# v0_2_1.net
KiCad netlist of a schematic drawn in EAGLE
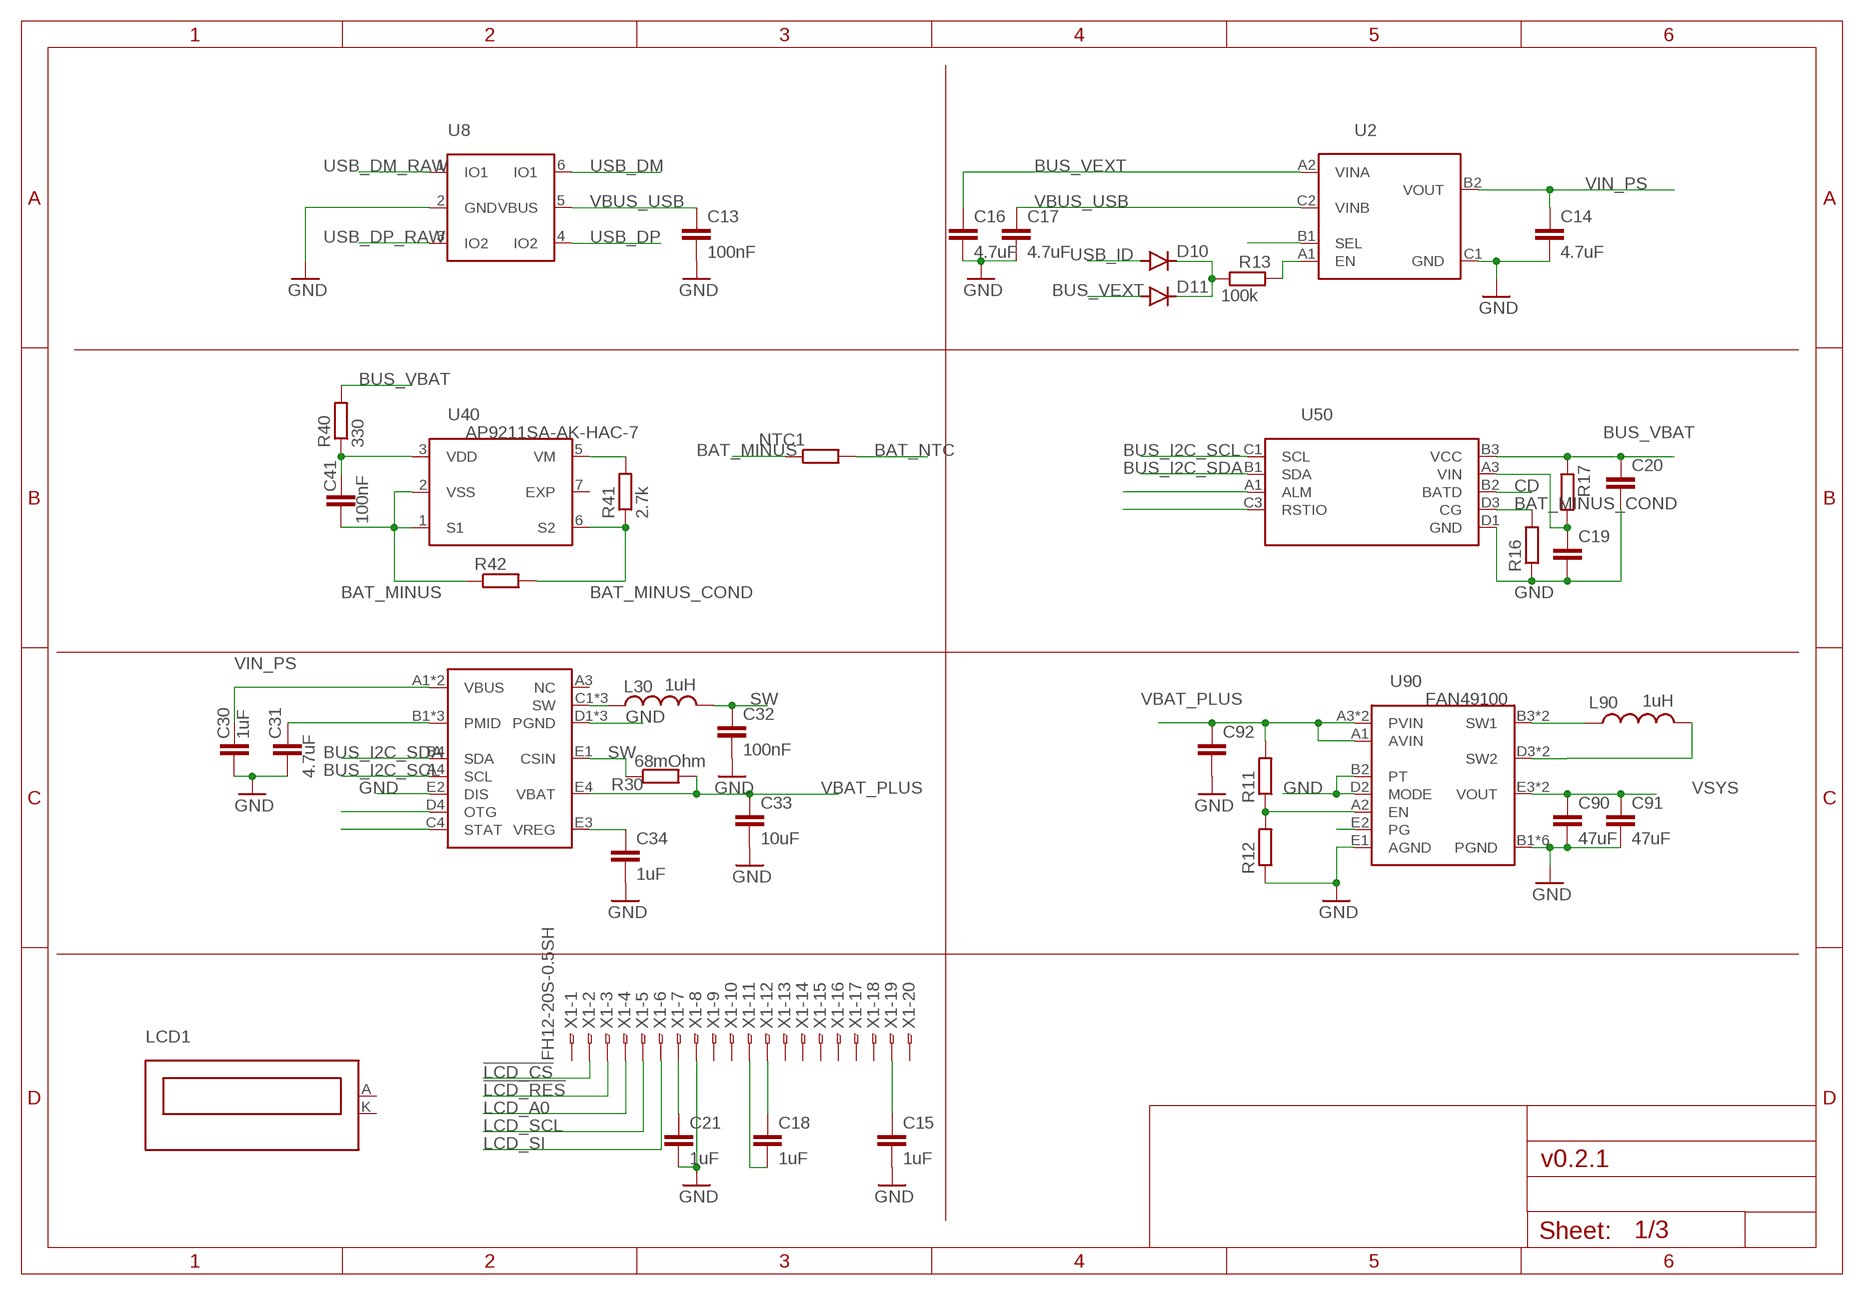
[diagram p0: schematic, sheet 1]
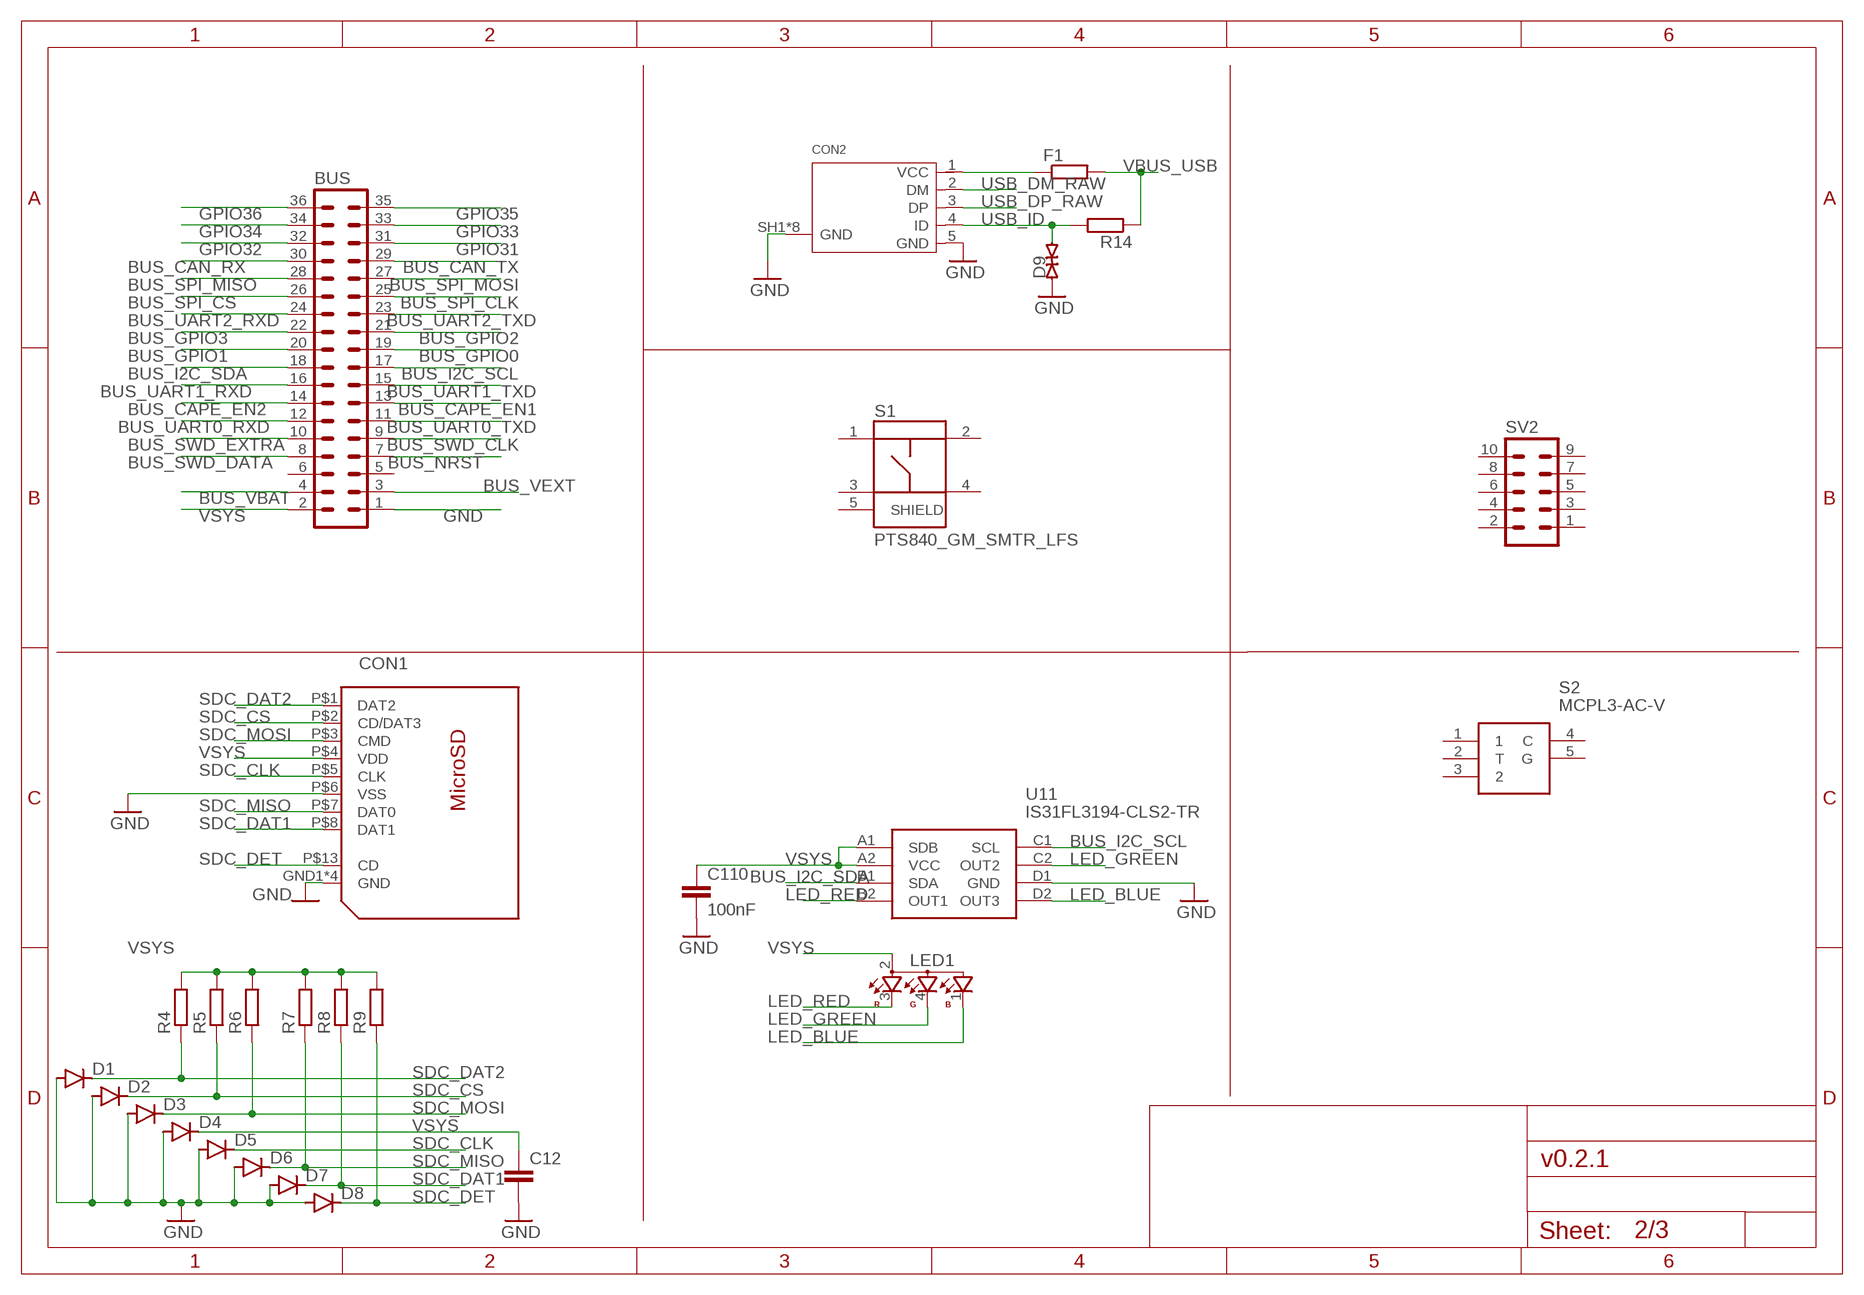
[diagram p1: schematic, sheet 2]
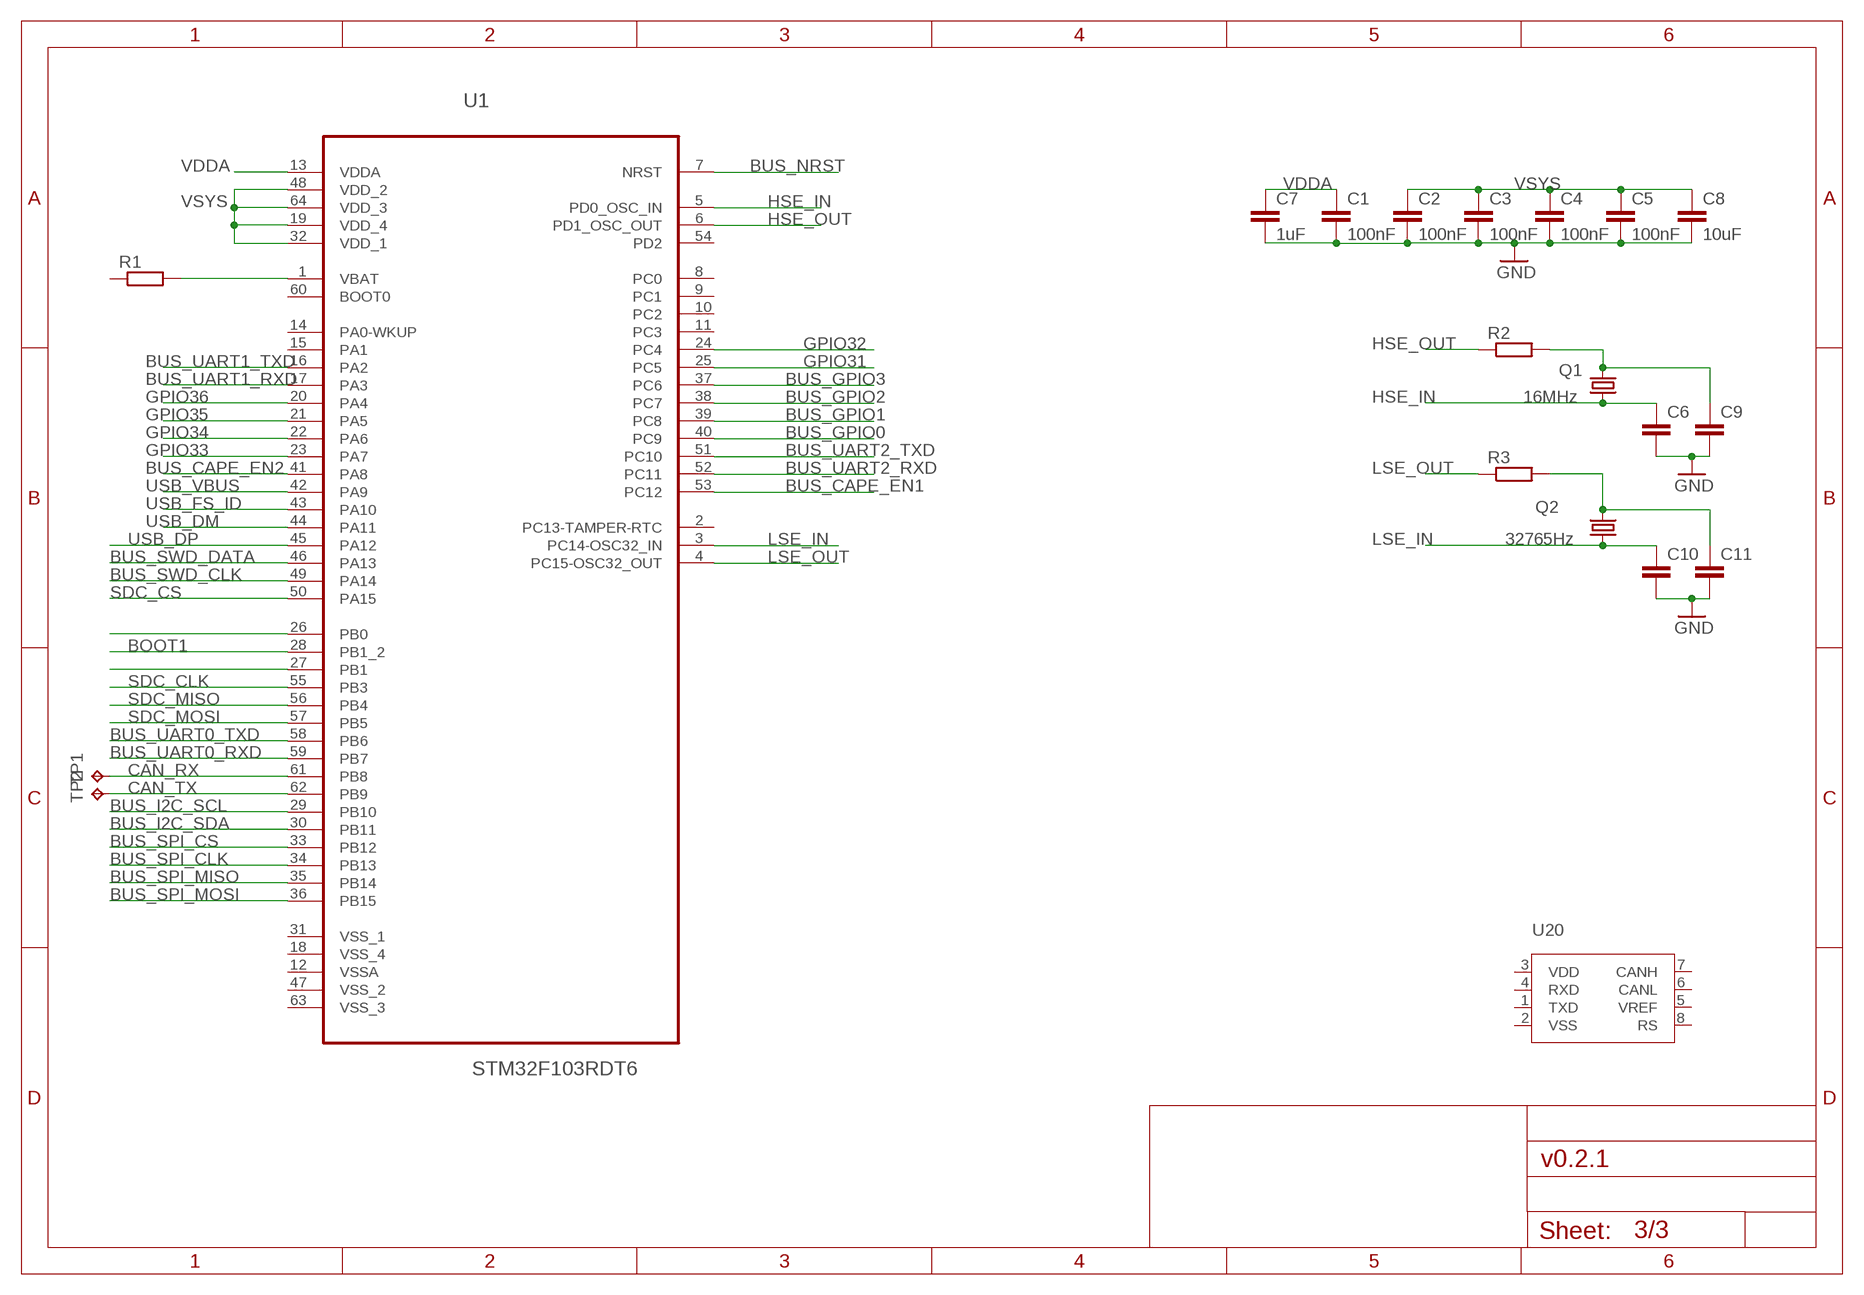
[diagram p2: schematic, sheet 3]

(export (version "E")
  (design (tool "Eeschema 10.0.6"))
  (components
    (comp (ref "C13")
      (value "100nF")
      (footprint "eagle-import:C0402")
      (libsource (lib "eagle-import") (part "C-EUC0402"))
    )
    (comp (ref "C14")
      (value "4.7uF")
      (footprint "eagle-import:C0603")
      (libsource (lib "eagle-import") (part "C-EUC0603"))
    )
    (comp (ref "C15")
      (value "1uF")
      (footprint "eagle-import:C0805")
      (libsource (lib "eagle-import") (part "C-EUC0805"))
    )
    (comp (ref "C16")
      (value "4.7uF")
      (footprint "eagle-import:C0603")
      (libsource (lib "eagle-import") (part "C-EUC0603"))
    )
    (comp (ref "C17")
      (value "4.7uF")
      (footprint "eagle-import:C0603")
      (libsource (lib "eagle-import") (part "C-EUC0603"))
    )
    (comp (ref "C18")
      (value "1uF")
      (footprint "eagle-import:C0805")
      (libsource (lib "eagle-import") (part "C-EUC0805"))
    )
    (comp (ref "C19")
      (value "C-EUC0402")
      (footprint "eagle-import:C0402")
      (libsource (lib "eagle-import") (part "C-EUC0402"))
    )
    (comp (ref "C20")
      (value "C-EUC0402")
      (footprint "eagle-import:C0402")
      (libsource (lib "eagle-import") (part "C-EUC0402"))
    )
    (comp (ref "C21")
      (value "1uF")
      (footprint "eagle-import:C0603")
      (libsource (lib "eagle-import") (part "C-EUC0603"))
    )
    (comp (ref "C30")
      (value "1uF")
      (footprint "eagle-import:C0402")
      (libsource (lib "eagle-import") (part "C-EUC0402"))
    )
    (comp (ref "C31")
      (value "4.7uF")
      (footprint "eagle-import:C0603")
      (libsource (lib "eagle-import") (part "C-EUC0603"))
    )
    (comp (ref "C32")
      (value "100nF")
      (footprint "eagle-import:C0402")
      (libsource (lib "eagle-import") (part "C-EUC0402"))
    )
    (comp (ref "C33")
      (value "10uF")
      (footprint "eagle-import:C0603")
      (libsource (lib "eagle-import") (part "C-EUC0603"))
    )
    (comp (ref "C34")
      (value "1uF")
      (footprint "eagle-import:C0402")
      (libsource (lib "eagle-import") (part "C-EUC0402"))
    )
    (comp (ref "C41")
      (value "100nF")
      (footprint "eagle-import:C0402")
      (libsource (lib "eagle-import") (part "C-EUC0402"))
    )
    (comp (ref "C90")
      (value "47uF")
      (footprint "eagle-import:C0805")
      (libsource (lib "eagle-import") (part "C-EUC0805"))
    )
    (comp (ref "C91")
      (value "47uF")
      (footprint "eagle-import:C0805")
      (libsource (lib "eagle-import") (part "C-EUC0805"))
    )
    (comp (ref "C92")
      (value "C-EUC0805")
      (footprint "eagle-import:C0805")
      (libsource (lib "eagle-import") (part "C-EUC0805"))
    )
    (comp (ref "D10")
      (value "DIODE-SOD523")
      (footprint "eagle-import:SOD523")
      (libsource (lib "eagle-import") (part "DIODE-SOD523"))
    )
    (comp (ref "D11")
      (value "DIODE-SOD523")
      (footprint "eagle-import:SOD523")
      (libsource (lib "eagle-import") (part "DIODE-SOD523"))
    )
    (comp (ref "L30")
      (value "1uH")
      (footprint "eagle-import:L3230M")
      (libsource (lib "eagle-import") (part "DJNR3015"))
    )
    (comp (ref "L90")
      (value "1uH")
      (footprint "eagle-import:L3230M")
      (libsource (lib "eagle-import") (part "DJNR3015"))
    )
    (comp (ref "LCD1")
      (value "DEM-128064P-FGH-PW")
      (footprint "eagle-import:DEM128064PFGH-PW")
      (libsource (lib "eagle-import") (part "DEM-128064P-FGH-PW"))
    )
    (comp (ref "NTC1")
      (value "R-EU_R0603")
      (footprint "eagle-import:R0603")
      (libsource (lib "eagle-import") (part "R-EU_R0603"))
    )
    (comp (ref "R11")
      (value "R-EU_R0402")
      (footprint "eagle-import:R0402")
      (libsource (lib "eagle-import") (part "R-EU_R0402"))
    )
    (comp (ref "R12")
      (value "R-EU_R0402")
      (footprint "eagle-import:R0402")
      (libsource (lib "eagle-import") (part "R-EU_R0402"))
    )
    (comp (ref "R13")
      (value "100k")
      (footprint "eagle-import:R0402")
      (libsource (lib "eagle-import") (part "R-EU_R0402"))
    )
    (comp (ref "R16")
      (value "R-EU_R0805")
      (footprint "eagle-import:R0805")
      (libsource (lib "eagle-import") (part "R-EU_R0805"))
    )
    (comp (ref "R17")
      (value "R-EU_R0402")
      (footprint "eagle-import:R0402")
      (libsource (lib "eagle-import") (part "R-EU_R0402"))
    )
    (comp (ref "R30")
      (value "68mOhm")
      (footprint "eagle-import:R0805")
      (libsource (lib "eagle-import") (part "R-EU_R0805"))
    )
    (comp (ref "R40")
      (value "330")
      (footprint "eagle-import:R0402")
      (libsource (lib "eagle-import") (part "R-EU_R0402"))
    )
    (comp (ref "R41")
      (value "2.7k")
      (footprint "eagle-import:R0402")
      (libsource (lib "eagle-import") (part "R-EU_R0402"))
    )
    (comp (ref "R42")
      (value "R-EU_R0603")
      (footprint "eagle-import:R0603")
      (libsource (lib "eagle-import") (part "R-EU_R0603"))
    )
    (comp (ref "U2")
      (value "FPF1320")
      (footprint "eagle-import:BGA6C50P2X3_146X96X60")
      (libsource (lib "eagle-import") (part "FPF1320"))
    )
    (comp (ref "U8")
      (value "USBLC6-2P6")
      (footprint "eagle-import:SOTFL50P160X60-6")
      (libsource (lib "eagle-import") (part "USBLC6-2P6"))
    )
    (comp (ref "U30")
      (value "FAN54015")
      (footprint "eagle-import:BGA20C40P4X5_196X187X55")
      (libsource (lib "eagle-import") (part "FAN54015"))
    )
    (comp (ref "U40")
      (value "AP9211SA-AK-HAC-7")
      (footprint "eagle-import:DFN200X300X60-7N")
      (fields (field (name "MF") "Diodes Inc."))
      (libsource (lib "eagle-import") (part "AP9211SA-AK-HAC-7"))
    )
    (comp (ref "U50")
      (value "STC3115")
      (footprint "eagle-import:BGA12C40P4X3_137X201X65")
      (libsource (lib "eagle-import") (part "STC3115"))
    )
    (comp (ref "U90")
      (value "FAN49100")
      (footprint "eagle-import:BGA20C40P4X5_201X161X60")
      (libsource (lib "eagle-import") (part "FAN49100"))
    )
    (comp (ref "X1")
      (value "FH12-20S-0.5SH")
      (footprint "eagle-import:FH12-20S-0.5SH")
      (fields (field (name "MPN") "FH12-20S-0.5SH(55)"))
      (libsource (lib "eagle-import") (part "FH12-20S-0.5SH"))
    )
    (comp (ref "BUS")
      (value "MA18-2")
      (footprint "eagle-import:MA18-2")
      (libsource (lib "eagle-import") (part "MA18-2"))
    )
    (comp (ref "C12")
      (value "C-EUC0402")
      (footprint "eagle-import:C0402")
      (libsource (lib "eagle-import") (part "C-EUC0402"))
    )
    (comp (ref "C110")
      (value "100nF")
      (footprint "eagle-import:C0402")
      (libsource (lib "eagle-import") (part "C-EUC0402"))
    )
    (comp (ref "CON1")
      (value "112J-TXAR")
      (footprint "eagle-import:112J")
      (libsource (lib "eagle-import") (part "112J-TXAR"))
    )
    (comp (ref "CON2")
      (value "10118194-0001LF")
      (footprint "eagle-import:10118194")
      (libsource (lib "eagle-import") (part "10118194-0001LF"))
    )
    (comp (ref "D1")
      (value "DIODE-SOD523")
      (footprint "eagle-import:SOD523")
      (libsource (lib "eagle-import") (part "DIODE-SOD523"))
    )
    (comp (ref "D2")
      (value "DIODE-SOD523")
      (footprint "eagle-import:SOD523")
      (libsource (lib "eagle-import") (part "DIODE-SOD523"))
    )
    (comp (ref "D3")
      (value "DIODE-SOD523")
      (footprint "eagle-import:SOD523")
      (libsource (lib "eagle-import") (part "DIODE-SOD523"))
    )
    (comp (ref "D4")
      (value "DIODE-SOD523")
      (footprint "eagle-import:SOD523")
      (libsource (lib "eagle-import") (part "DIODE-SOD523"))
    )
    (comp (ref "D5")
      (value "DIODE-SOD523")
      (footprint "eagle-import:SOD523")
      (libsource (lib "eagle-import") (part "DIODE-SOD523"))
    )
    (comp (ref "D6")
      (value "DIODE-SOD523")
      (footprint "eagle-import:SOD523")
      (libsource (lib "eagle-import") (part "DIODE-SOD523"))
    )
    (comp (ref "D7")
      (value "DIODE-SOD523")
      (footprint "eagle-import:SOD523")
      (libsource (lib "eagle-import") (part "DIODE-SOD523"))
    )
    (comp (ref "D8")
      (value "DIODE-SOD523")
      (footprint "eagle-import:SOD523")
      (libsource (lib "eagle-import") (part "DIODE-SOD523"))
    )
    (comp (ref "D9")
      (value "ESD9B5.0ST5G")
      (footprint "eagle-import:SOD1006X40")
      (libsource (lib "eagle-import") (part "ESD9B5.0ST5G"))
    )
    (comp (ref "F1")
      (value "R-EU_R0603")
      (footprint "eagle-import:R0603")
      (libsource (lib "eagle-import") (part "R-EU_R0603"))
    )
    (comp (ref "LED1")
      (value "OSTB1204C1E")
      (footprint "eagle-import:321015RGB")
      (libsource (lib "eagle-import") (part "OSTB1204C1E"))
    )
    (comp (ref "R4")
      (value "R-EU_R0402")
      (footprint "eagle-import:R0402")
      (libsource (lib "eagle-import") (part "R-EU_R0402"))
    )
    (comp (ref "R5")
      (value "R-EU_R0402")
      (footprint "eagle-import:R0402")
      (libsource (lib "eagle-import") (part "R-EU_R0402"))
    )
    (comp (ref "R6")
      (value "R-EU_R0402")
      (footprint "eagle-import:R0402")
      (libsource (lib "eagle-import") (part "R-EU_R0402"))
    )
    (comp (ref "R7")
      (value "R-EU_R0402")
      (footprint "eagle-import:R0402")
      (libsource (lib "eagle-import") (part "R-EU_R0402"))
    )
    (comp (ref "R8")
      (value "R-EU_R0402")
      (footprint "eagle-import:R0402")
      (libsource (lib "eagle-import") (part "R-EU_R0402"))
    )
    (comp (ref "R9")
      (value "R-EU_R0402")
      (footprint "eagle-import:R0402")
      (libsource (lib "eagle-import") (part "R-EU_R0402"))
    )
    (comp (ref "R14")
      (value "R-EU_R0402")
      (footprint "eagle-import:R0402")
      (libsource (lib "eagle-import") (part "R-EU_R0402"))
    )
    (comp (ref "S1")
      (value "PTS840_GM_SMTR_LFS")
      (footprint "eagle-import:SW_PTS840GMSMTRLFS")
      (fields (field (name "MF") "C&K") (field (name "MP") "PTS840 GM SMTR LFS"))
      (libsource (lib "eagle-import") (part "PTS840_GM_SMTR_LFS"))
    )
    (comp (ref "S2")
      (value "MCPL3-AC-V")
      (footprint "eagle-import:MCPL3-AC-V")
      (libsource (lib "eagle-import") (part "MCPL3-AC-V"))
    )
    (comp (ref "SV2")
      (value "MA05-2")
      (footprint "eagle-import:MA05-2")
      (libsource (lib "eagle-import") (part "MA05-2"))
    )
    (comp (ref "U11")
      (value "IS31FL3194-CLS2-TR")
      (footprint "eagle-import:BGA8C40P2X4_99X159X42")
      (fields (field (name "MOUSER_PART_NUMBER") "870-IS31FL3194CLS2TR"))
      (libsource (lib "eagle-import") (part "IS31FL3194-CLS2-TR"))
    )
    (comp (ref "C1")
      (value "100nF")
      (footprint "eagle-import:C0402")
      (libsource (lib "eagle-import") (part "C-EUC0402"))
    )
    (comp (ref "C2")
      (value "100nF")
      (footprint "eagle-import:C0402")
      (libsource (lib "eagle-import") (part "C-EUC0402"))
    )
    (comp (ref "C3")
      (value "100nF")
      (footprint "eagle-import:C0402")
      (libsource (lib "eagle-import") (part "C-EUC0402"))
    )
    (comp (ref "C4")
      (value "100nF")
      (footprint "eagle-import:C0402")
      (libsource (lib "eagle-import") (part "C-EUC0402"))
    )
    (comp (ref "C5")
      (value "100nF")
      (footprint "eagle-import:C0402")
      (libsource (lib "eagle-import") (part "C-EUC0402"))
    )
    (comp (ref "C6")
      (value "C-EUC0402")
      (footprint "eagle-import:C0402")
      (libsource (lib "eagle-import") (part "C-EUC0402"))
    )
    (comp (ref "C7")
      (value "1uF")
      (footprint "eagle-import:C0402")
      (libsource (lib "eagle-import") (part "C-EUC0402"))
    )
    (comp (ref "C8")
      (value "10uF")
      (footprint "eagle-import:C0603")
      (libsource (lib "eagle-import") (part "C-EUC0603"))
    )
    (comp (ref "C9")
      (value "C-EUC0402")
      (footprint "eagle-import:C0402")
      (libsource (lib "eagle-import") (part "C-EUC0402"))
    )
    (comp (ref "C10")
      (value "C-EUC0402")
      (footprint "eagle-import:C0402")
      (libsource (lib "eagle-import") (part "C-EUC0402"))
    )
    (comp (ref "C11")
      (value "C-EUC0402")
      (footprint "eagle-import:C0402")
      (libsource (lib "eagle-import") (part "C-EUC0402"))
    )
    (comp (ref "Q1")
      (value "16MHz")
      (footprint "eagle-import:3.2X2.5_KX-7")
      (libsource (lib "eagle-import") (part "KX-7"))
    )
    (comp (ref "Q2")
      (value "32765Hz")
      (footprint "eagle-import:3.2X1.5")
      (libsource (lib "eagle-import") (part "KX-327-NHF"))
    )
    (comp (ref "R1")
      (value "R-EU_R0402")
      (footprint "eagle-import:R0402")
      (libsource (lib "eagle-import") (part "R-EU_R0402"))
    )
    (comp (ref "R2")
      (value "R-EU_R0402")
      (footprint "eagle-import:R0402")
      (libsource (lib "eagle-import") (part "R-EU_R0402"))
    )
    (comp (ref "R3")
      (value "R-EU_R0402")
      (footprint "eagle-import:R0402")
      (libsource (lib "eagle-import") (part "R-EU_R0402"))
    )
    (comp (ref "TP1")
      (value "TPB1,27")
      (footprint "eagle-import:B1,27")
      (libsource (lib "eagle-import") (part "TPB1,27"))
    )
    (comp (ref "TP2")
      (value "TPB1,27")
      (footprint "eagle-import:B1,27")
      (libsource (lib "eagle-import") (part "TPB1,27"))
    )
    (comp (ref "U1")
      (value "STM32F103RDT6")
      (footprint "eagle-import:QFP50P1200X1200X160-64N")
      (fields (field (name "MF") "STMicroelectronics"))
      (libsource (lib "eagle-import") (part "STM32F103RDT6"))
    )
    (comp (ref "U20")
      (value "MCP2551")
      (footprint "eagle-import:SOIC8")
      (libsource (lib "eagle-import") (part "MCP2551"))
    )
  )
  (nets
    (net (code "1") (name "BAT_MINUS") (class "Default")
      (node (ref "C41") (pin "2") (pinfunction "2_2") (pintype "passive"))
      (node (ref "NTC1") (pin "1") (pinfunction "1_1") (pintype "passive"))
      (node (ref "R42") (pin "1") (pinfunction "1_1") (pintype "passive"))
      (node (ref "U40") (pin "1") (pinfunction "S1_1") (pintype "output"))
      (node (ref "U40") (pin "2") (pinfunction "VSS_2") (pintype "power_in"))
    )
    (net (code "2") (name "BAT_MINUS_COND") (class "Default")
      (node (ref "R16") (pin "2") (pinfunction "2_2") (pintype "passive"))
      (node (ref "R41") (pin "1") (pinfunction "1_1") (pintype "passive"))
      (node (ref "R42") (pin "2") (pinfunction "2_2") (pintype "passive"))
      (node (ref "U40") (pin "6") (pinfunction "S2_6") (pintype "output"))
      (node (ref "U50") (pin "D3") (pinfunction "CG_D3") (pintype "bidirectional"))
    )
    (net (code "3") (name "BAT_NTC") (class "Default")
      (node (ref "NTC1") (pin "2") (pinfunction "2_2") (pintype "passive"))
    )
    (net (code "4") (name "BOOT1") (class "Default")
      (node (ref "U1") (pin "28") (pinfunction "PB1_2_28") (pintype "bidirectional"))
    )
    (net (code "5") (name "BUS_CAN_RX") (class "Default")
      (node (ref "BUS") (pin "30") (pinfunction "30_30") (pintype "passive"))
    )
    (net (code "6") (name "BUS_CAN_TX") (class "Default")
      (node (ref "BUS") (pin "29") (pinfunction "29_29") (pintype "passive"))
    )
    (net (code "7") (name "BUS_CAPE_EN1") (class "Default")
      (node (ref "BUS") (pin "13") (pinfunction "13_13") (pintype "passive"))
      (node (ref "U1") (pin "53") (pinfunction "PC12_53") (pintype "bidirectional"))
    )
    (net (code "8") (name "BUS_CAPE_EN2") (class "Default")
      (node (ref "BUS") (pin "14") (pinfunction "14_14") (pintype "passive"))
      (node (ref "U1") (pin "41") (pinfunction "PA8_41") (pintype "bidirectional"))
    )
    (net (code "9") (name "BUS_GPIO0") (class "Default")
      (node (ref "BUS") (pin "19") (pinfunction "19_19") (pintype "passive"))
      (node (ref "U1") (pin "40") (pinfunction "PC9_40") (pintype "bidirectional"))
    )
    (net (code "10") (name "BUS_GPIO1") (class "Default")
      (node (ref "BUS") (pin "20") (pinfunction "20_20") (pintype "passive"))
      (node (ref "U1") (pin "39") (pinfunction "PC8_39") (pintype "bidirectional"))
    )
    (net (code "11") (name "BUS_GPIO2") (class "Default")
      (node (ref "BUS") (pin "21") (pinfunction "21_21") (pintype "passive"))
      (node (ref "U1") (pin "38") (pinfunction "PC7_38") (pintype "bidirectional"))
    )
    (net (code "12") (name "BUS_GPIO3") (class "Default")
      (node (ref "BUS") (pin "22") (pinfunction "22_22") (pintype "passive"))
      (node (ref "U1") (pin "37") (pinfunction "PC6_37") (pintype "bidirectional"))
    )
    (net (code "13") (name "BUS_I2C_SCL") (class "Default")
      (node (ref "BUS") (pin "17") (pinfunction "17_17") (pintype "passive"))
      (node (ref "U1") (pin "29") (pinfunction "PB10_29") (pintype "bidirectional"))
      (node (ref "U11") (pin "C1") (pinfunction "SCL_C1") (pintype "bidirectional"))
      (node (ref "U30") (pin "A4") (pinfunction "SCL_A4") (pintype "bidirectional"))
      (node (ref "U50") (pin "C1") (pinfunction "SCL_C1") (pintype "bidirectional"))
    )
    (net (code "14") (name "BUS_I2C_SDA") (class "Default")
      (node (ref "BUS") (pin "18") (pinfunction "18_18") (pintype "passive"))
      (node (ref "U1") (pin "30") (pinfunction "PB11_30") (pintype "bidirectional"))
      (node (ref "U11") (pin "B1") (pinfunction "SDA_B1") (pintype "bidirectional"))
      (node (ref "U30") (pin "B4") (pinfunction "SDA_B4") (pintype "bidirectional"))
      (node (ref "U50") (pin "B1") (pinfunction "SDA_B1") (pintype "bidirectional"))
    )
    (net (code "15") (name "BUS_NRST") (class "Default")
      (node (ref "BUS") (pin "7") (pinfunction "7_7") (pintype "passive"))
      (node (ref "U1") (pin "7") (pinfunction "NRST_7") (pintype "output"))
    )
    (net (code "16") (name "BUS_SPI_CLK") (class "Default")
      (node (ref "BUS") (pin "25") (pinfunction "25_25") (pintype "passive"))
      (node (ref "U1") (pin "34") (pinfunction "PB13_34") (pintype "bidirectional"))
    )
    (net (code "17") (name "BUS_SPI_CS") (class "Default")
      (node (ref "BUS") (pin "26") (pinfunction "26_26") (pintype "passive"))
      (node (ref "U1") (pin "33") (pinfunction "PB12_33") (pintype "bidirectional"))
    )
    (net (code "18") (name "BUS_SPI_MISO") (class "Default")
      (node (ref "BUS") (pin "28") (pinfunction "28_28") (pintype "passive"))
      (node (ref "U1") (pin "35") (pinfunction "PB14_35") (pintype "bidirectional"))
    )
    (net (code "19") (name "BUS_SPI_MOSI") (class "Default")
      (node (ref "BUS") (pin "27") (pinfunction "27_27") (pintype "passive"))
      (node (ref "U1") (pin "36") (pinfunction "PB15_36") (pintype "bidirectional"))
    )
    (net (code "20") (name "BUS_SWD_CLK") (class "Default")
      (node (ref "BUS") (pin "9") (pinfunction "9_9") (pintype "passive"))
      (node (ref "U1") (pin "49") (pinfunction "PA14_49") (pintype "bidirectional"))
    )
    (net (code "21") (name "BUS_SWD_DATA") (class "Default")
      (node (ref "BUS") (pin "8") (pinfunction "8_8") (pintype "passive"))
      (node (ref "U1") (pin "46") (pinfunction "PA13_46") (pintype "bidirectional"))
    )
    (net (code "22") (name "BUS_SWD_EXTRA") (class "Default")
      (node (ref "BUS") (pin "10") (pinfunction "10_10") (pintype "passive"))
    )
    (net (code "23") (name "BUS_UART0_RXD") (class "Default")
      (node (ref "BUS") (pin "12") (pinfunction "12_12") (pintype "passive"))
      (node (ref "U1") (pin "59") (pinfunction "PB7_59") (pintype "power_in"))
    )
    (net (code "24") (name "BUS_UART0_TXD") (class "Default")
      (node (ref "BUS") (pin "11") (pinfunction "11_11") (pintype "passive"))
      (node (ref "U1") (pin "58") (pinfunction "PB6_58") (pintype "bidirectional"))
    )
    (net (code "25") (name "BUS_UART1_RXD") (class "Default")
      (node (ref "BUS") (pin "16") (pinfunction "16_16") (pintype "passive"))
      (node (ref "U1") (pin "17") (pinfunction "PA3_17") (pintype "bidirectional"))
    )
    (net (code "26") (name "BUS_UART1_TXD") (class "Default")
      (node (ref "BUS") (pin "15") (pinfunction "15_15") (pintype "passive"))
      (node (ref "U1") (pin "16") (pinfunction "PA2_16") (pintype "bidirectional"))
    )
    (net (code "27") (name "BUS_UART2_RXD") (class "Default")
      (node (ref "BUS") (pin "24") (pinfunction "24_24") (pintype "passive"))
      (node (ref "U1") (pin "52") (pinfunction "PC11_52") (pintype "bidirectional"))
    )
    (net (code "28") (name "BUS_UART2_TXD") (class "Default")
      (node (ref "BUS") (pin "23") (pinfunction "23_23") (pintype "passive"))
      (node (ref "U1") (pin "51") (pinfunction "PC10_51") (pintype "bidirectional"))
    )
    (net (code "29") (name "BUS_VBAT") (class "Default")
      (node (ref "BUS") (pin "4") (pinfunction "4_4") (pintype "passive"))
      (node (ref "C20") (pin "1") (pinfunction "1_1") (pintype "passive"))
      (node (ref "R17") (pin "1") (pinfunction "1_1") (pintype "passive"))
      (node (ref "R40") (pin "2") (pinfunction "2_2") (pintype "passive"))
      (node (ref "U50") (pin "B3") (pinfunction "VCC_B3") (pintype "bidirectional"))
    )
    (net (code "30") (name "BUS_VEXT") (class "Default")
      (node (ref "BUS") (pin "3") (pinfunction "3_3") (pintype "passive"))
      (node (ref "C16") (pin "1") (pinfunction "1_1") (pintype "passive"))
      (node (ref "D11") (pin "A") (pinfunction "A_A") (pintype "passive"))
      (node (ref "U2") (pin "A2") (pinfunction "VINA_A2") (pintype "bidirectional"))
    )
    (net (code "31") (name "CAN_RX") (class "Default")
      (node (ref "TP1") (pin "TP") (pinfunction "TP_TP") (pintype "input"))
      (node (ref "U1") (pin "61") (pinfunction "PB8_61") (pintype "bidirectional"))
    )
    (net (code "32") (name "CAN_TX") (class "Default")
      (node (ref "TP2") (pin "TP") (pinfunction "TP_TP") (pintype "input"))
      (node (ref "U1") (pin "62") (pinfunction "PB9_62") (pintype "bidirectional"))
    )
    (net (code "33") (name "CD") (class "Default")
      (node (ref "U50") (pin "B2") (pinfunction "BATD_B2") (pintype "bidirectional"))
    )
    (net (code "34") (name "EXP") (class "Default")
      (node (ref "U40") (pin "7") (pinfunction "EXP_7") (pintype "power_in"))
    )
    (net (code "35") (name "GND") (class "Default")
      (node (ref "BUS") (pin "1") (pinfunction "1_1") (pintype "passive"))
      (node (ref "C1") (pin "2") (pinfunction "2_2") (pintype "passive"))
      (node (ref "C10") (pin "2") (pinfunction "2_2") (pintype "passive"))
      (node (ref "C11") (pin "2") (pinfunction "2_2") (pintype "passive"))
      (node (ref "C110") (pin "2") (pinfunction "2_2") (pintype "passive"))
      (node (ref "C12") (pin "2") (pinfunction "2_2") (pintype "passive"))
      (node (ref "C13") (pin "2") (pinfunction "2_2") (pintype "passive"))
      (node (ref "C14") (pin "2") (pinfunction "2_2") (pintype "passive"))
      (node (ref "C15") (pin "2") (pinfunction "2_2") (pintype "passive"))
      (node (ref "C16") (pin "2") (pinfunction "2_2") (pintype "passive"))
      (node (ref "C17") (pin "2") (pinfunction "2_2") (pintype "passive"))
      (node (ref "C19") (pin "2") (pinfunction "2_2") (pintype "passive"))
      (node (ref "C2") (pin "2") (pinfunction "2_2") (pintype "passive"))
      (node (ref "C20") (pin "2") (pinfunction "2_2") (pintype "passive"))
      (node (ref "C21") (pin "2") (pinfunction "2_2") (pintype "passive"))
      (node (ref "C3") (pin "2") (pinfunction "2_2") (pintype "passive"))
      (node (ref "C30") (pin "2") (pinfunction "2_2") (pintype "passive"))
      (node (ref "C31") (pin "2") (pinfunction "2_2") (pintype "passive"))
      (node (ref "C32") (pin "2") (pinfunction "2_2") (pintype "passive"))
      (node (ref "C33") (pin "2") (pinfunction "2_2") (pintype "passive"))
      (node (ref "C34") (pin "2") (pinfunction "2_2") (pintype "passive"))
      (node (ref "C4") (pin "2") (pinfunction "2_2") (pintype "passive"))
      (node (ref "C5") (pin "2") (pinfunction "2_2") (pintype "passive"))
      (node (ref "C6") (pin "2") (pinfunction "2_2") (pintype "passive"))
      (node (ref "C7") (pin "2") (pinfunction "2_2") (pintype "passive"))
      (node (ref "C8") (pin "2") (pinfunction "2_2") (pintype "passive"))
      (node (ref "C9") (pin "2") (pinfunction "2_2") (pintype "passive"))
      (node (ref "C90") (pin "2") (pinfunction "2_2") (pintype "passive"))
      (node (ref "C91") (pin "2") (pinfunction "2_2") (pintype "passive"))
      (node (ref "C92") (pin "2") (pinfunction "2_2") (pintype "passive"))
      (node (ref "CON1") (pin "GND1") (pinfunction "GND_GND1") (pintype "power_in"))
      (node (ref "CON1") (pin "GND2") (pinfunction "GND_GND2") (pintype "power_in"))
      (node (ref "CON1") (pin "GND3") (pinfunction "GND_GND3") (pintype "power_in"))
      (node (ref "CON1") (pin "GND4") (pinfunction "GND_GND4") (pintype "power_in"))
      (node (ref "CON1") (pin "P$6") (pinfunction "VSS_P$6") (pintype "bidirectional"))
      (node (ref "CON2") (pin "5") (pinfunction "GND_5") (pintype "bidirectional"))
      (node (ref "CON2") (pin "SH1") (pinfunction "GND_SH1") (pintype "bidirectional"))
      (node (ref "CON2") (pin "SH2") (pinfunction "GND_SH2") (pintype "bidirectional"))
      (node (ref "CON2") (pin "SH3") (pinfunction "GND_SH3") (pintype "bidirectional"))
      (node (ref "CON2") (pin "SH4") (pinfunction "GND_SH4") (pintype "bidirectional"))
      (node (ref "CON2") (pin "SH5") (pinfunction "GND_SH5") (pintype "bidirectional"))
      (node (ref "CON2") (pin "SH6") (pinfunction "GND_SH6") (pintype "bidirectional"))
      (node (ref "CON2") (pin "SH7") (pinfunction "GND_SH7") (pintype "bidirectional"))
      (node (ref "CON2") (pin "SH8") (pinfunction "GND_SH8") (pintype "bidirectional"))
      (node (ref "D1") (pin "A") (pinfunction "A_A") (pintype "passive"))
      (node (ref "D2") (pin "A") (pinfunction "A_A") (pintype "passive"))
      (node (ref "D3") (pin "A") (pinfunction "A_A") (pintype "passive"))
      (node (ref "D4") (pin "A") (pinfunction "A_A") (pintype "passive"))
      (node (ref "D5") (pin "A") (pinfunction "A_A") (pintype "passive"))
      (node (ref "D6") (pin "A") (pinfunction "A_A") (pintype "passive"))
      (node (ref "D7") (pin "A") (pinfunction "A_A") (pintype "passive"))
      (node (ref "D8") (pin "A") (pinfunction "A_A") (pintype "passive"))
      (node (ref "D9") (pin "1") (pinfunction "A_1") (pintype "passive"))
      (node (ref "R12") (pin "1") (pinfunction "1_1") (pintype "passive"))
      (node (ref "R16") (pin "1") (pinfunction "1_1") (pintype "passive"))
      (node (ref "U11") (pin "D1") (pinfunction "GND_D1") (pintype "bidirectional"))
      (node (ref "U2") (pin "C1") (pinfunction "GND_C1") (pintype "bidirectional"))
      (node (ref "U30") (pin "D1") (pinfunction "PGND_D1") (pintype "bidirectional"))
      (node (ref "U30") (pin "D2") (pinfunction "PGND_D2") (pintype "bidirectional"))
      (node (ref "U30") (pin "D3") (pinfunction "PGND_D3") (pintype "bidirectional"))
      (node (ref "U30") (pin "E2") (pinfunction "DIS_E2") (pintype "bidirectional"))
      (node (ref "U50") (pin "D1") (pinfunction "GND_D1") (pintype "bidirectional"))
      (node (ref "U8") (pin "2") (pinfunction "GND_2") (pintype "bidirectional"))
      (node (ref "U90") (pin "B1") (pinfunction "PGND_B1") (pintype "bidirectional"))
      (node (ref "U90") (pin "B2") (pinfunction "PT_B2") (pintype "bidirectional"))
      (node (ref "U90") (pin "C1") (pinfunction "PGND_C1") (pintype "bidirectional"))
      (node (ref "U90") (pin "C2") (pinfunction "PGND_C2") (pintype "bidirectional"))
      (node (ref "U90") (pin "C3") (pinfunction "PGND_C3") (pintype "bidirectional"))
      (node (ref "U90") (pin "C4") (pinfunction "PGND_C4") (pintype "bidirectional"))
      (node (ref "U90") (pin "D1") (pinfunction "PGND_D1") (pintype "bidirectional"))
      (node (ref "U90") (pin "D2") (pinfunction "MODE_D2") (pintype "bidirectional"))
      (node (ref "U90") (pin "E1") (pinfunction "AGND_E1") (pintype "bidirectional"))
      (node (ref "X1") (pin "8") (pinfunction "1_8") (pintype "passive"))
    )
    (net (code "36") (name "GPIO31") (class "Default")
      (node (ref "BUS") (pin "31") (pinfunction "31_31") (pintype "passive"))
      (node (ref "U1") (pin "25") (pinfunction "PC5_25") (pintype "bidirectional"))
    )
    (net (code "37") (name "GPIO32") (class "Default")
      (node (ref "BUS") (pin "32") (pinfunction "32_32") (pintype "passive"))
      (node (ref "U1") (pin "24") (pinfunction "PC4_24") (pintype "passive"))
    )
    (net (code "38") (name "GPIO33") (class "Default")
      (node (ref "BUS") (pin "33") (pinfunction "33_33") (pintype "passive"))
      (node (ref "U1") (pin "23") (pinfunction "PA7_23") (pintype "power_in"))
    )
    (net (code "39") (name "GPIO34") (class "Default")
      (node (ref "BUS") (pin "34") (pinfunction "34_34") (pintype "passive"))
      (node (ref "U1") (pin "22") (pinfunction "PA6_22") (pintype "bidirectional"))
    )
    (net (code "40") (name "GPIO35") (class "Default")
      (node (ref "BUS") (pin "35") (pinfunction "35_35") (pintype "passive"))
      (node (ref "U1") (pin "21") (pinfunction "PA5_21") (pintype "bidirectional"))
    )
    (net (code "41") (name "GPIO36") (class "Default")
      (node (ref "BUS") (pin "36") (pinfunction "36_36") (pintype "passive"))
      (node (ref "U1") (pin "20") (pinfunction "PA4_20") (pintype "bidirectional"))
    )
    (net (code "42") (name "HSE_IN") (class "Default")
      (node (ref "C6") (pin "1") (pinfunction "1_1") (pintype "passive"))
      (node (ref "Q1") (pin "1") (pinfunction "1_1") (pintype "passive"))
      (node (ref "U1") (pin "5") (pinfunction "PD0_OSC_IN_5") (pintype "input"))
    )
    (net (code "43") (name "HSE_OUT") (class "Default")
      (node (ref "R2") (pin "1") (pinfunction "1_1") (pintype "passive"))
      (node (ref "U1") (pin "6") (pinfunction "PD1_OSC_OUT_6") (pintype "output"))
    )
    (net (code "44") (name "LCD_A0") (class "Default")
      (node (ref "X1") (pin "4") (pinfunction "1_4") (pintype "passive"))
    )
    (net (code "45") (name "LCD_SCL") (class "Default")
      (node (ref "X1") (pin "5") (pinfunction "1_5") (pintype "passive"))
    )
    (net (code "46") (name "LCD_SI") (class "Default")
      (node (ref "X1") (pin "6") (pinfunction "1_6") (pintype "passive"))
    )
    (net (code "47") (name "LED_BLUE") (class "Default")
      (node (ref "LED1") (pin "1") (pinfunction "1_1") (pintype "passive"))
      (node (ref "U11") (pin "D2") (pinfunction "OUT3_D2") (pintype "bidirectional"))
    )
    (net (code "48") (name "LED_GREEN") (class "Default")
      (node (ref "LED1") (pin "4") (pinfunction "4_4") (pintype "passive"))
      (node (ref "U11") (pin "C2") (pinfunction "OUT2_C2") (pintype "bidirectional"))
    )
    (net (code "49") (name "LED_RED") (class "Default")
      (node (ref "LED1") (pin "3") (pinfunction "3_3") (pintype "passive"))
      (node (ref "U11") (pin "B2") (pinfunction "OUT1_B2") (pintype "bidirectional"))
    )
    (net (code "50") (name "LSE_IN") (class "Default")
      (node (ref "C10") (pin "1") (pinfunction "1_1") (pintype "passive"))
      (node (ref "Q2") (pin "1") (pinfunction "1_1") (pintype "passive"))
      (node (ref "U1") (pin "3") (pinfunction "PC14-OSC32_IN_3") (pintype "input"))
    )
    (net (code "51") (name "LSE_OUT") (class "Default")
      (node (ref "R3") (pin "1") (pinfunction "1_1") (pintype "passive"))
      (node (ref "U1") (pin "4") (pinfunction "PC15-OSC32_OUT_4") (pintype "output"))
    )
    (net (code "52") (name "Net-(C11-Pad1)") (class "Default")
      (node (ref "C11") (pin "1") (pinfunction "1_1") (pintype "passive"))
      (node (ref "Q2") (pin "2") (pinfunction "2_2") (pintype "passive"))
      (node (ref "R3") (pin "2") (pinfunction "2_2") (pintype "passive"))
    )
    (net (code "53") (name "Net-(C31-Pad1)") (class "Default")
      (node (ref "C31") (pin "1") (pinfunction "1_1") (pintype "passive"))
      (node (ref "U30") (pin "B1") (pinfunction "PMID_B1") (pintype "bidirectional"))
      (node (ref "U30") (pin "B2") (pinfunction "PMID_B2") (pintype "bidirectional"))
      (node (ref "U30") (pin "B3") (pinfunction "PMID_B3") (pintype "bidirectional"))
    )
    (net (code "54") (name "Net-(CON2-VCC)") (class "Default")
      (node (ref "CON2") (pin "1") (pinfunction "VCC_1") (pintype "bidirectional"))
      (node (ref "F1") (pin "1") (pinfunction "1_1") (pintype "passive"))
    )
    (net (code "55") (name "Net-(D10-PadC)") (class "Default")
      (node (ref "D10") (pin "C") (pinfunction "C_C") (pintype "passive"))
      (node (ref "D11") (pin "C") (pinfunction "C_C") (pintype "passive"))
      (node (ref "R13") (pin "1") (pinfunction "1_1") (pintype "passive"))
    )
    (net (code "56") (name "Net-(L30-Pad1)") (class "Default")
      (node (ref "L30") (pin "1") (pinfunction "1_1") (pintype "passive"))
      (node (ref "U30") (pin "C1") (pinfunction "SW_C1") (pintype "bidirectional"))
      (node (ref "U30") (pin "C2") (pinfunction "SW_C2") (pintype "bidirectional"))
      (node (ref "U30") (pin "C3") (pinfunction "SW_C3") (pintype "bidirectional"))
    )
    (net (code "57") (name "Net-(L90-Pad1)") (class "Default")
      (node (ref "L90") (pin "1") (pinfunction "1_1") (pintype "passive"))
      (node (ref "U90") (pin "B3") (pinfunction "SW1_B3") (pintype "bidirectional"))
      (node (ref "U90") (pin "B4") (pinfunction "SW1_B4") (pintype "bidirectional"))
    )
    (net (code "58") (name "Net-(L90-Pad2)") (class "Default")
      (node (ref "L90") (pin "2") (pinfunction "2_2") (pintype "passive"))
      (node (ref "U90") (pin "D3") (pinfunction "SW2_D3") (pintype "bidirectional"))
      (node (ref "U90") (pin "D4") (pinfunction "SW2_D4") (pintype "bidirectional"))
    )
    (net (code "59") (name "Net-(Q1-2)") (class "Default")
      (node (ref "C9") (pin "1") (pinfunction "1_1") (pintype "passive"))
      (node (ref "Q1") (pin "3") (pinfunction "2_3") (pintype "passive"))
      (node (ref "R2") (pin "2") (pinfunction "2_2") (pintype "passive"))
    )
    (net (code "60") (name "Net-(U1-VBAT)") (class "Default")
      (node (ref "R1") (pin "2") (pinfunction "2_2") (pintype "passive"))
      (node (ref "U1") (pin "1") (pinfunction "VBAT_1") (pintype "input"))
    )
    (net (code "61") (name "Net-(U2-EN)") (class "Default")
      (node (ref "R13") (pin "2") (pinfunction "2_2") (pintype "passive"))
      (node (ref "U2") (pin "A1") (pinfunction "EN_A1") (pintype "bidirectional"))
    )
    (net (code "62") (name "Net-(U30-VREG)") (class "Default")
      (node (ref "C34") (pin "1") (pinfunction "1_1") (pintype "passive"))
      (node (ref "U30") (pin "E3") (pinfunction "VREG_E3") (pintype "bidirectional"))
    )
    (net (code "63") (name "Net-(U40-VDD)") (class "Default")
      (node (ref "C41") (pin "1") (pinfunction "1_1") (pintype "passive"))
      (node (ref "R40") (pin "1") (pinfunction "1_1") (pintype "passive"))
      (node (ref "U40") (pin "3") (pinfunction "VDD_3") (pintype "power_in"))
    )
    (net (code "64") (name "Net-(U40-VM)") (class "Default")
      (node (ref "R41") (pin "2") (pinfunction "2_2") (pintype "passive"))
      (node (ref "U40") (pin "5") (pinfunction "VM_5") (pintype "input"))
    )
    (net (code "65") (name "Net-(U50-VIN)") (class "Default")
      (node (ref "C19") (pin "1") (pinfunction "1_1") (pintype "passive"))
      (node (ref "R17") (pin "2") (pinfunction "2_2") (pintype "passive"))
      (node (ref "U50") (pin "A3") (pinfunction "VIN_A3") (pintype "bidirectional"))
    )
    (net (code "66") (name "Net-(U90-EN)") (class "Default")
      (node (ref "R11") (pin "1") (pinfunction "1_1") (pintype "passive"))
      (node (ref "R12") (pin "2") (pinfunction "2_2") (pintype "passive"))
      (node (ref "U90") (pin "A2") (pinfunction "EN_A2") (pintype "bidirectional"))
    )
    (net (code "67") (name "Net-(X1C-1)") (class "Default")
      (node (ref "C18") (pin "2") (pinfunction "2_2") (pintype "passive"))
      (node (ref "X1") (pin "11") (pinfunction "1_11") (pintype "passive"))
    )
    (net (code "68") (name "Net-(X1D-1)") (class "Default")
      (node (ref "C18") (pin "1") (pinfunction "1_1") (pintype "passive"))
      (node (ref "X1") (pin "12") (pinfunction "1_12") (pintype "passive"))
    )
    (net (code "69") (name "Net-(X1K-1)") (class "Default")
      (node (ref "C15") (pin "1") (pinfunction "1_1") (pintype "passive"))
      (node (ref "X1") (pin "19") (pinfunction "1_19") (pintype "passive"))
    )
    (net (code "70") (name "Net-(X1R-1)") (class "Default")
      (node (ref "C21") (pin "1") (pinfunction "1_1") (pintype "passive"))
      (node (ref "X1") (pin "7") (pinfunction "1_7") (pintype "passive"))
    )
    (net (code "71") (name "SDC_CLK") (class "Default")
      (node (ref "CON1") (pin "P$5") (pinfunction "CLK_P$5") (pintype "bidirectional"))
      (node (ref "D5") (pin "C") (pinfunction "C_C") (pintype "passive"))
      (node (ref "U1") (pin "55") (pinfunction "PB3_55") (pintype "bidirectional"))
    )
    (net (code "72") (name "SDC_CS") (class "Default")
      (node (ref "CON1") (pin "P$2") (pinfunction "CD/DAT3_P$2") (pintype "input"))
      (node (ref "D2") (pin "C") (pinfunction "C_C") (pintype "passive"))
      (node (ref "R5") (pin "1") (pinfunction "1_1") (pintype "passive"))
      (node (ref "U1") (pin "50") (pinfunction "PA15_50") (pintype "bidirectional"))
    )
    (net (code "73") (name "SDC_DAT1") (class "Default")
      (node (ref "CON1") (pin "P$8") (pinfunction "DAT1_P$8") (pintype "power_in"))
      (node (ref "D7") (pin "C") (pinfunction "C_C") (pintype "passive"))
      (node (ref "R8") (pin "1") (pinfunction "1_1") (pintype "passive"))
    )
    (net (code "74") (name "SDC_DAT2") (class "Default")
      (node (ref "CON1") (pin "P$1") (pinfunction "DAT2_P$1") (pintype "output"))
      (node (ref "D1") (pin "C") (pinfunction "C_C") (pintype "passive"))
      (node (ref "R4") (pin "1") (pinfunction "1_1") (pintype "passive"))
    )
    (net (code "75") (name "SDC_DET") (class "Default")
      (node (ref "CON1") (pin "P$13") (pinfunction "CD_P$13") (pintype "power_in"))
      (node (ref "D8") (pin "C") (pinfunction "C_C") (pintype "passive"))
      (node (ref "R9") (pin "1") (pinfunction "1_1") (pintype "passive"))
    )
    (net (code "76") (name "SDC_MISO") (class "Default")
      (node (ref "CON1") (pin "P$7") (pinfunction "DAT0_P$7") (pintype "power_in"))
      (node (ref "D6") (pin "C") (pinfunction "C_C") (pintype "passive"))
      (node (ref "R7") (pin "1") (pinfunction "1_1") (pintype "passive"))
      (node (ref "U1") (pin "56") (pinfunction "PB4_56") (pintype "bidirectional"))
    )
    (net (code "77") (name "SDC_MOSI") (class "Default")
      (node (ref "CON1") (pin "P$3") (pinfunction "CMD_P$3") (pintype "input"))
      (node (ref "D3") (pin "C") (pinfunction "C_C") (pintype "passive"))
      (node (ref "R6") (pin "1") (pinfunction "1_1") (pintype "passive"))
      (node (ref "U1") (pin "57") (pinfunction "PB5_57") (pintype "bidirectional"))
    )
    (net (code "78") (name "SW") (class "Default")
      (node (ref "C32") (pin "1") (pinfunction "1_1") (pintype "passive"))
      (node (ref "L30") (pin "2") (pinfunction "2_2") (pintype "passive"))
      (node (ref "R30") (pin "1") (pinfunction "1_1") (pintype "passive"))
      (node (ref "U30") (pin "E1") (pinfunction "CSIN_E1") (pintype "bidirectional"))
    )
    (net (code "79") (name "USB_DM") (class "Default")
      (node (ref "U1") (pin "44") (pinfunction "PA11_44") (pintype "bidirectional"))
      (node (ref "U8") (pin "6") (pinfunction "IO1_6") (pintype "bidirectional"))
    )
    (net (code "80") (name "USB_DM_RAW") (class "Default")
      (node (ref "CON2") (pin "2") (pinfunction "DM_2") (pintype "bidirectional"))
      (node (ref "U8") (pin "1") (pinfunction "IO1_1") (pintype "bidirectional"))
    )
    (net (code "81") (name "USB_DP") (class "Default")
      (node (ref "U1") (pin "45") (pinfunction "PA12_45") (pintype "bidirectional"))
      (node (ref "U8") (pin "4") (pinfunction "IO2_4") (pintype "bidirectional"))
    )
    (net (code "82") (name "USB_DP_RAW") (class "Default")
      (node (ref "CON2") (pin "3") (pinfunction "DP_3") (pintype "bidirectional"))
      (node (ref "U8") (pin "3") (pinfunction "IO2_3") (pintype "bidirectional"))
    )
    (net (code "83") (name "USB_FS_ID") (class "Default")
      (node (ref "U1") (pin "43") (pinfunction "PA10_43") (pintype "bidirectional"))
    )
    (net (code "84") (name "USB_ID") (class "Default")
      (node (ref "CON2") (pin "4") (pinfunction "ID_4") (pintype "bidirectional"))
      (node (ref "D10") (pin "A") (pinfunction "A_A") (pintype "passive"))
      (node (ref "D9") (pin "2") (pinfunction "C_2") (pintype "passive"))
      (node (ref "R14") (pin "2") (pinfunction "2_2") (pintype "passive"))
    )
    (net (code "85") (name "USB_VBUS") (class "Default")
      (node (ref "U1") (pin "42") (pinfunction "PA9_42") (pintype "bidirectional"))
    )
    (net (code "86") (name "VBAT_PLUS") (class "Default")
      (node (ref "C33") (pin "1") (pinfunction "1_1") (pintype "passive"))
      (node (ref "C92") (pin "1") (pinfunction "1_1") (pintype "passive"))
      (node (ref "R11") (pin "2") (pinfunction "2_2") (pintype "passive"))
      (node (ref "R30") (pin "2") (pinfunction "2_2") (pintype "passive"))
      (node (ref "U30") (pin "E4") (pinfunction "VBAT_E4") (pintype "bidirectional"))
      (node (ref "U90") (pin "A1") (pinfunction "AVIN_A1") (pintype "bidirectional"))
      (node (ref "U90") (pin "A3") (pinfunction "PVIN_A3") (pintype "bidirectional"))
      (node (ref "U90") (pin "A4") (pinfunction "PVIN_A4") (pintype "bidirectional"))
    )
    (net (code "87") (name "VBUS_USB") (class "Default")
      (node (ref "C13") (pin "1") (pinfunction "1_1") (pintype "passive"))
      (node (ref "C17") (pin "1") (pinfunction "1_1") (pintype "passive"))
      (node (ref "F1") (pin "2") (pinfunction "2_2") (pintype "passive"))
      (node (ref "R14") (pin "1") (pinfunction "1_1") (pintype "passive"))
      (node (ref "U2") (pin "C2") (pinfunction "VINB_C2") (pintype "bidirectional"))
      (node (ref "U8") (pin "5") (pinfunction "VBUS_5") (pintype "bidirectional"))
    )
    (net (code "88") (name "VDDA") (class "Default")
      (node (ref "C1") (pin "1") (pinfunction "1_1") (pintype "passive"))
      (node (ref "C7") (pin "1") (pinfunction "1_1") (pintype "passive"))
      (node (ref "U1") (pin "13") (pinfunction "VDDA_13") (pintype "power_in"))
    )
    (net (code "89") (name "VIN_PS") (class "Default")
      (node (ref "C14") (pin "1") (pinfunction "1_1") (pintype "passive"))
      (node (ref "C30") (pin "1") (pinfunction "1_1") (pintype "passive"))
      (node (ref "U2") (pin "B2") (pinfunction "VOUT_B2") (pintype "bidirectional"))
      (node (ref "U30") (pin "A1") (pinfunction "VBUS_A1") (pintype "bidirectional"))
      (node (ref "U30") (pin "A2") (pinfunction "VBUS_A2") (pintype "bidirectional"))
    )
    (net (code "90") (name "VSYS") (class "Default")
      (node (ref "BUS") (pin "2") (pinfunction "2_2") (pintype "passive"))
      (node (ref "C110") (pin "1") (pinfunction "1_1") (pintype "passive"))
      (node (ref "C12") (pin "1") (pinfunction "1_1") (pintype "passive"))
      (node (ref "C2") (pin "1") (pinfunction "1_1") (pintype "passive"))
      (node (ref "C3") (pin "1") (pinfunction "1_1") (pintype "passive"))
      (node (ref "C4") (pin "1") (pinfunction "1_1") (pintype "passive"))
      (node (ref "C5") (pin "1") (pinfunction "1_1") (pintype "passive"))
      (node (ref "C8") (pin "1") (pinfunction "1_1") (pintype "passive"))
      (node (ref "C90") (pin "1") (pinfunction "1_1") (pintype "passive"))
      (node (ref "C91") (pin "1") (pinfunction "1_1") (pintype "passive"))
      (node (ref "CON1") (pin "P$4") (pinfunction "VDD_P$4") (pintype "input"))
      (node (ref "D4") (pin "C") (pinfunction "C_C") (pintype "passive"))
      (node (ref "LED1") (pin "2") (pinfunction "2_2") (pintype "passive"))
      (node (ref "R4") (pin "2") (pinfunction "2_2") (pintype "passive"))
      (node (ref "R5") (pin "2") (pinfunction "2_2") (pintype "passive"))
      (node (ref "R6") (pin "2") (pinfunction "2_2") (pintype "passive"))
      (node (ref "R7") (pin "2") (pinfunction "2_2") (pintype "passive"))
      (node (ref "R8") (pin "2") (pinfunction "2_2") (pintype "passive"))
      (node (ref "R9") (pin "2") (pinfunction "2_2") (pintype "passive"))
      (node (ref "U1") (pin "19") (pinfunction "VDD_4_19") (pintype "power_in"))
      (node (ref "U1") (pin "32") (pinfunction "VDD_1_32") (pintype "power_in"))
      (node (ref "U1") (pin "48") (pinfunction "VDD_2_48") (pintype "power_in"))
      (node (ref "U1") (pin "64") (pinfunction "VDD_3_64") (pintype "power_in"))
      (node (ref "U11") (pin "A1") (pinfunction "SDB_A1") (pintype "bidirectional"))
      (node (ref "U11") (pin "A2") (pinfunction "VCC_A2") (pintype "bidirectional"))
      (node (ref "U90") (pin "E3") (pinfunction "VOUT_E3") (pintype "bidirectional"))
      (node (ref "U90") (pin "E4") (pinfunction "VOUT_E4") (pintype "bidirectional"))
    )
    (net (code "91") (name "unconnected-(BUS-Pad5)") (class "Default")
      (node (ref "BUS") (pin "5") (pinfunction "5_5") (pintype "passive"))
    )
    (net (code "92") (name "unconnected-(BUS-Pad6)") (class "Default")
      (node (ref "BUS") (pin "6") (pinfunction "6_6") (pintype "passive"))
    )
    (net (code "93") (name "unconnected-(LCD1-P$1-PadA)") (class "Default")
      (node (ref "LCD1") (pin "A") (pinfunction "P$1_A") (pintype "bidirectional"))
    )
    (net (code "94") (name "unconnected-(LCD1-P$2-PadK)") (class "Default")
      (node (ref "LCD1") (pin "K") (pinfunction "P$2_K") (pintype "bidirectional"))
    )
    (net (code "95") (name "unconnected-(R1-Pad1)") (class "Default")
      (node (ref "R1") (pin "1") (pinfunction "1_1") (pintype "passive"))
    )
    (net (code "96") (name "unconnected-(S1-Pad1)") (class "Default")
      (node (ref "S1") (pin "1") (pinfunction "1_1") (pintype "passive"))
    )
    (net (code "97") (name "unconnected-(S1-Pad2)") (class "Default")
      (node (ref "S1") (pin "2") (pinfunction "2_2") (pintype "passive"))
    )
    (net (code "98") (name "unconnected-(S1-Pad3)") (class "Default")
      (node (ref "S1") (pin "3") (pinfunction "3_3") (pintype "passive"))
    )
    (net (code "99") (name "unconnected-(S1-Pad4)") (class "Default")
      (node (ref "S1") (pin "4") (pinfunction "4_4") (pintype "passive"))
    )
    (net (code "100") (name "unconnected-(S1-SHIELD-Pad5)") (class "Default")
      (node (ref "S1") (pin "5") (pinfunction "SHIELD_5") (pintype "passive"))
    )
    (net (code "101") (name "unconnected-(S2-2-Pad3)") (class "Default")
      (node (ref "S2") (pin "3") (pinfunction "2_3") (pintype "bidirectional"))
    )
    (net (code "102") (name "unconnected-(S2-C-Pad4)") (class "Default")
      (node (ref "S2") (pin "4") (pinfunction "C_4") (pintype "bidirectional"))
    )
    (net (code "103") (name "unconnected-(S2-G-Pad5)") (class "Default")
      (node (ref "S2") (pin "5") (pinfunction "G_5") (pintype "bidirectional"))
    )
    (net (code "104") (name "unconnected-(S2-Pad1)") (class "Default")
      (node (ref "S2") (pin "1") (pinfunction "1_1") (pintype "bidirectional"))
    )
    (net (code "105") (name "unconnected-(S2-T-Pad2)") (class "Default")
      (node (ref "S2") (pin "2") (pinfunction "T_2") (pintype "bidirectional"))
    )
    (net (code "106") (name "unconnected-(SV2-Pad1)") (class "Default")
      (node (ref "SV2") (pin "1") (pinfunction "1_1") (pintype "passive"))
    )
    (net (code "107") (name "unconnected-(SV2-Pad2)") (class "Default")
      (node (ref "SV2") (pin "2") (pinfunction "2_2") (pintype "passive"))
    )
    (net (code "108") (name "unconnected-(SV2-Pad3)") (class "Default")
      (node (ref "SV2") (pin "3") (pinfunction "3_3") (pintype "passive"))
    )
    (net (code "109") (name "unconnected-(SV2-Pad4)") (class "Default")
      (node (ref "SV2") (pin "4") (pinfunction "4_4") (pintype "passive"))
    )
    (net (code "110") (name "unconnected-(SV2-Pad5)") (class "Default")
      (node (ref "SV2") (pin "5") (pinfunction "5_5") (pintype "passive"))
    )
    (net (code "111") (name "unconnected-(SV2-Pad6)") (class "Default")
      (node (ref "SV2") (pin "6") (pinfunction "6_6") (pintype "passive"))
    )
    (net (code "112") (name "unconnected-(SV2-Pad7)") (class "Default")
      (node (ref "SV2") (pin "7") (pinfunction "7_7") (pintype "passive"))
    )
    (net (code "113") (name "unconnected-(SV2-Pad8)") (class "Default")
      (node (ref "SV2") (pin "8") (pinfunction "8_8") (pintype "passive"))
    )
    (net (code "114") (name "unconnected-(SV2-Pad9)") (class "Default")
      (node (ref "SV2") (pin "9") (pinfunction "9_9") (pintype "passive"))
    )
    (net (code "115") (name "unconnected-(SV2-Pad10)") (class "Default")
      (node (ref "SV2") (pin "10") (pinfunction "10_10") (pintype "passive"))
    )
    (net (code "116") (name "unconnected-(U1-BOOT0-Pad60)") (class "Default")
      (node (ref "U1") (pin "60") (pinfunction "BOOT0_60") (pintype "passive"))
    )
    (net (code "117") (name "unconnected-(U1-PA0-WKUP-Pad14)") (class "Default")
      (node (ref "U1") (pin "14") (pinfunction "PA0-WKUP_14") (pintype "bidirectional"))
    )
    (net (code "118") (name "unconnected-(U1-PA1-Pad15)") (class "Default")
      (node (ref "U1") (pin "15") (pinfunction "PA1_15") (pintype "bidirectional"))
    )
    (net (code "119") (name "unconnected-(U1-PB0-Pad26)") (class "Default")
      (node (ref "U1") (pin "26") (pinfunction "PB0_26") (pintype "bidirectional"))
    )
    (net (code "120") (name "unconnected-(U1-PB1-Pad27)") (class "Default")
      (node (ref "U1") (pin "27") (pinfunction "PB1_27") (pintype "bidirectional"))
    )
    (net (code "121") (name "unconnected-(U1-PC0-Pad8)") (class "Default")
      (node (ref "U1") (pin "8") (pinfunction "PC0_8") (pintype "bidirectional"))
    )
    (net (code "122") (name "unconnected-(U1-PC1-Pad9)") (class "Default")
      (node (ref "U1") (pin "9") (pinfunction "PC1_9") (pintype "bidirectional"))
    )
    (net (code "123") (name "unconnected-(U1-PC2-Pad10)") (class "Default")
      (node (ref "U1") (pin "10") (pinfunction "PC2_10") (pintype "bidirectional"))
    )
    (net (code "124") (name "unconnected-(U1-PC3-Pad11)") (class "Default")
      (node (ref "U1") (pin "11") (pinfunction "PC3_11") (pintype "bidirectional"))
    )
    (net (code "125") (name "unconnected-(U1-PC13-TAMPER-RTC-Pad2)") (class "Default")
      (node (ref "U1") (pin "2") (pinfunction "PC13-TAMPER-RTC_2") (pintype "input"))
    )
    (net (code "126") (name "unconnected-(U1-PD2-Pad54)") (class "Default")
      (node (ref "U1") (pin "54") (pinfunction "PD2_54") (pintype "bidirectional"))
    )
    (net (code "127") (name "unconnected-(U1-VSSA-Pad12)") (class "Default")
      (node (ref "U1") (pin "12") (pinfunction "VSSA_12") (pintype "passive"))
    )
    (net (code "128") (name "unconnected-(U1-VSS_1-Pad31)") (class "Default")
      (node (ref "U1") (pin "31") (pinfunction "VSS_1_31") (pintype "passive"))
    )
    (net (code "129") (name "unconnected-(U1-VSS_2-Pad47)") (class "Default")
      (node (ref "U1") (pin "47") (pinfunction "VSS_2_47") (pintype "passive"))
    )
    (net (code "130") (name "unconnected-(U1-VSS_3-Pad63)") (class "Default")
      (node (ref "U1") (pin "63") (pinfunction "VSS_3_63") (pintype "passive"))
    )
    (net (code "131") (name "unconnected-(U1-VSS_4-Pad18)") (class "Default")
      (node (ref "U1") (pin "18") (pinfunction "VSS_4_18") (pintype "passive"))
    )
    (net (code "132") (name "unconnected-(U2-SEL-PadB1)") (class "Default")
      (node (ref "U2") (pin "B1") (pinfunction "SEL_B1") (pintype "bidirectional"))
    )
    (net (code "133") (name "unconnected-(U20-CANH-Pad7)") (class "Default")
      (node (ref "U20") (pin "7") (pinfunction "CANH_7") (pintype "bidirectional"))
    )
    (net (code "134") (name "unconnected-(U20-CANL-Pad6)") (class "Default")
      (node (ref "U20") (pin "6") (pinfunction "CANL_6") (pintype "bidirectional"))
    )
    (net (code "135") (name "unconnected-(U20-RS-Pad8)") (class "Default")
      (node (ref "U20") (pin "8") (pinfunction "RS_8") (pintype "bidirectional"))
    )
    (net (code "136") (name "unconnected-(U20-RXD-Pad4)") (class "Default")
      (node (ref "U20") (pin "4") (pinfunction "RXD_4") (pintype "bidirectional"))
    )
    (net (code "137") (name "unconnected-(U20-TXD-Pad1)") (class "Default")
      (node (ref "U20") (pin "1") (pinfunction "TXD_1") (pintype "bidirectional"))
    )
    (net (code "138") (name "unconnected-(U20-VDD-Pad3)") (class "Default")
      (node (ref "U20") (pin "3") (pinfunction "VDD_3") (pintype "bidirectional"))
    )
    (net (code "139") (name "unconnected-(U20-VREF-Pad5)") (class "Default")
      (node (ref "U20") (pin "5") (pinfunction "VREF_5") (pintype "bidirectional"))
    )
    (net (code "140") (name "unconnected-(U20-VSS-Pad2)") (class "Default")
      (node (ref "U20") (pin "2") (pinfunction "VSS_2") (pintype "bidirectional"))
    )
    (net (code "141") (name "unconnected-(U30-NC-PadA3)") (class "Default")
      (node (ref "U30") (pin "A3") (pinfunction "NC_A3") (pintype "no_connect"))
    )
    (net (code "142") (name "unconnected-(U30-OTG-PadD4)") (class "Default")
      (node (ref "U30") (pin "D4") (pinfunction "OTG_D4") (pintype "bidirectional"))
    )
    (net (code "143") (name "unconnected-(U30-STAT-PadC4)") (class "Default")
      (node (ref "U30") (pin "C4") (pinfunction "STAT_C4") (pintype "bidirectional"))
    )
    (net (code "144") (name "unconnected-(U50-ALM-PadA1)") (class "Default")
      (node (ref "U50") (pin "A1") (pinfunction "ALM_A1") (pintype "bidirectional"))
    )
    (net (code "145") (name "unconnected-(U50-RSTIO-PadC3)") (class "Default")
      (node (ref "U50") (pin "C3") (pinfunction "RSTIO_C3") (pintype "bidirectional"))
    )
    (net (code "146") (name "unconnected-(U90-PG-PadE2)") (class "Default")
      (node (ref "U90") (pin "E2") (pinfunction "PG_E2") (pintype "bidirectional"))
    )
    (net (code "147") (name "unconnected-(X1-Pad1)") (class "Default")
      (node (ref "X1") (pin "1") (pinfunction "1_1") (pintype "passive"))
    )
    (net (code "148") (name "unconnected-(X1B-1-Pad10)") (class "Default")
      (node (ref "X1") (pin "10") (pinfunction "1_10") (pintype "passive"))
    )
    (net (code "149") (name "unconnected-(X1E-1-Pad13)") (class "Default")
      (node (ref "X1") (pin "13") (pinfunction "1_13") (pintype "passive"))
    )
    (net (code "150") (name "unconnected-(X1F-1-Pad14)") (class "Default")
      (node (ref "X1") (pin "14") (pinfunction "1_14") (pintype "passive"))
    )
    (net (code "151") (name "unconnected-(X1G-1-Pad15)") (class "Default")
      (node (ref "X1") (pin "15") (pinfunction "1_15") (pintype "passive"))
    )
    (net (code "152") (name "unconnected-(X1H-1-Pad16)") (class "Default")
      (node (ref "X1") (pin "16") (pinfunction "1_16") (pintype "passive"))
    )
    (net (code "153") (name "unconnected-(X1I-1-Pad17)") (class "Default")
      (node (ref "X1") (pin "17") (pinfunction "1_17") (pintype "passive"))
    )
    (net (code "154") (name "unconnected-(X1J-1-Pad18)") (class "Default")
      (node (ref "X1") (pin "18") (pinfunction "1_18") (pintype "passive"))
    )
    (net (code "155") (name "unconnected-(X1M-1-Pad20)") (class "Default")
      (node (ref "X1") (pin "20") (pinfunction "1_20") (pintype "passive"))
    )
    (net (code "156") (name "unconnected-(X1T-1-Pad9)") (class "Default")
      (node (ref "X1") (pin "9") (pinfunction "1_9") (pintype "passive"))
    )
    (net (code "157") (name "~{LCD_CS}") (class "Default")
      (node (ref "X1") (pin "2") (pinfunction "1_2") (pintype "passive"))
    )
    (net (code "158") (name "~{LCD_RES}") (class "Default")
      (node (ref "X1") (pin "3") (pinfunction "1_3") (pintype "passive"))
    )
  )
)
